# RS485.net
KiCad netlist of a schematic drawn in Altium Designer
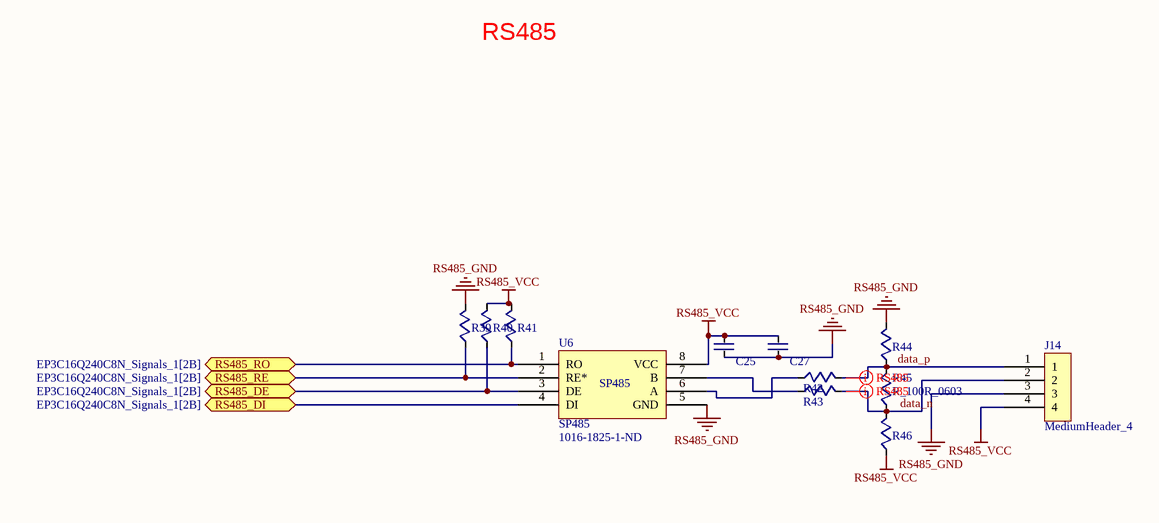
[diagram p0: RS485.SchDoc]

(export (version "E")
  (design (tool "Eeschema 10.0.6"))
  (components
    (comp (ref "C25")
      (value "100n Cer")
      (footprint "CN-SMD-0805")
      (description "CAP CER 0.1UF 25V 10% X7R 0805")
      (libsource (lib "EngineersLife") (part "CAPC0805_104"))
    )
    (comp (ref "C27")
      (value "10n Cer")
      (footprint "CN-SMD-0805")
      (description "CAP CER 10000PF 100V X7R 0805")
      (libsource (lib "EngineersLife") (part "CAPC0805_103"))
    )
    (comp (ref "J14")
      (value "MediumHeader_4")
      (footprint "Medium - Header 4")
      (libsource (lib "IO_Lib") (part "MediumHeader_4"))
    )
    (comp (ref "R39")
      (value "R_10K_0603")
      (footprint "RESC_0603")
      (description "RES 10.0K OHM 1/10W 1% 0603 SMD")
      (libsource (lib "IO_Lib") (part "RES0603_10K"))
    )
    (comp (ref "R40")
      (value "R_10K_0603")
      (footprint "RESC_0603")
      (description "RES 10.0K OHM 1/10W 1% 0603 SMD")
      (libsource (lib "IO_Lib") (part "RES0603_10K"))
    )
    (comp (ref "R41")
      (value "R_4K99_0603")
      (footprint "RESC_0603")
      (description "RES 4.99K OHM 1/10W 1% 0603 SMD")
      (libsource (lib "IO_Lib") (part "RES0603_4K99"))
    )
    (comp (ref "R42")
      (value "R_10K_0603")
      (footprint "RESC_0603")
      (description "RES 10.0K OHM 1/10W 1% 0603 SMD")
      (libsource (lib "IO_Lib") (part "RES0603_10K"))
    )
    (comp (ref "R43")
      (value "R_10R_0603")
      (footprint "RESC_0603")
      (description "RES 10.0 OHM 1/10W 0603 SMD")
      (libsource (lib "IO_Lib") (part "RES0603_10R"))
    )
    (comp (ref "R44")
      (value "R_2K_0603")
      (footprint "RESC_0603")
      (description "RES 2K OHM 1/10W 0603 SMD")
      (libsource (lib "IO_Lib") (part "RES0603_2K"))
    )
    (comp (ref "R45")
      (value "R_100R_0603")
      (footprint "RESC_0603")
      (description "RES 100 OHM 1/10W 5% 0603 SMD")
      (libsource (lib "IO_Lib") (part "RES0603_100R"))
    )
    (comp (ref "R46")
      (value "R_2K_0603")
      (footprint "RESC_0603")
      (description "RES 2K OHM 1/10W 0603 SMD")
      (libsource (lib "IO_Lib") (part "RES0603_2K"))
    )
    (comp (ref "U6")
      (value "SP485")
      (footprint "SOP8")
      (description "IC TXRX RS485 HALF DUPLEX 8SOIC")
      (fields (field (name "SUPPLIER PART NUMBER 1") "1016-1825-1-ND"))
      (libsource (lib "EngineersLife") (part "SP485"))
    )
  )
  (nets
    (net (code "1") (name "/RS485_DE") (class "Default")
      (node (ref "R40") (pin "1") (pinfunction "1_1") (pintype "passive"))
      (node (ref "U6") (pin "3") (pinfunction "DE_3") (pintype "passive"))
    )
    (net (code "2") (name "/RS485_DI") (class "Default")
      (node (ref "U6") (pin "4") (pinfunction "DI_4") (pintype "passive"))
    )
    (net (code "3") (name "/RS485_RE") (class "Default")
      (node (ref "R39") (pin "1") (pinfunction "1_1") (pintype "passive"))
      (node (ref "U6") (pin "2") (pinfunction "RE*_2") (pintype "passive"))
    )
    (net (code "4") (name "/RS485_RO") (class "Default")
      (node (ref "R41") (pin "1") (pinfunction "1_1") (pintype "passive"))
      (node (ref "U6") (pin "1") (pinfunction "RO_1") (pintype "passive"))
    )
    (net (code "5") (name "/data_n") (class "Default")
      (node (ref "J14") (pin "2") (pinfunction "2_2") (pintype "passive"))
      (node (ref "R43") (pin "2") (pinfunction "2_2") (pintype "passive"))
      (node (ref "R45") (pin "1") (pinfunction "1_1") (pintype "passive"))
      (node (ref "R46") (pin "2") (pinfunction "2_2") (pintype "passive"))
    )
    (net (code "6") (name "/data_p") (class "Default")
      (node (ref "J14") (pin "1") (pinfunction "1_1") (pintype "passive"))
      (node (ref "R42") (pin "2") (pinfunction "2_2") (pintype "passive"))
      (node (ref "R44") (pin "1") (pinfunction "1_1") (pintype "passive"))
      (node (ref "R45") (pin "2") (pinfunction "2_2") (pintype "passive"))
    )
    (net (code "7") (name "Net-(U6-A)") (class "Default")
      (node (ref "R42") (pin "1") (pinfunction "1_1") (pintype "passive"))
      (node (ref "U6") (pin "6") (pinfunction "A_6") (pintype "passive"))
    )
    (net (code "8") (name "Net-(U6-B)") (class "Default")
      (node (ref "R43") (pin "1") (pinfunction "1_1") (pintype "passive"))
      (node (ref "U6") (pin "7") (pinfunction "B_7") (pintype "passive"))
    )
    (net (code "9") (name "RS485_GND") (class "Default")
      (node (ref "C25") (pin "1") (pinfunction "1_1") (pintype "passive"))
      (node (ref "C27") (pin "1") (pinfunction "1_1") (pintype "passive"))
      (node (ref "J14") (pin "3") (pinfunction "3_3") (pintype "passive"))
      (node (ref "R39") (pin "2") (pinfunction "2_2") (pintype "passive"))
      (node (ref "R44") (pin "2") (pinfunction "2_2") (pintype "passive"))
      (node (ref "U6") (pin "5") (pinfunction "GND_5") (pintype "passive"))
    )
    (net (code "10") (name "RS485_VCC") (class "Default")
      (node (ref "C25") (pin "2") (pinfunction "2_2") (pintype "passive"))
      (node (ref "C27") (pin "2") (pinfunction "2_2") (pintype "passive"))
      (node (ref "J14") (pin "4") (pinfunction "4_4") (pintype "passive"))
      (node (ref "R40") (pin "2") (pinfunction "2_2") (pintype "passive"))
      (node (ref "R41") (pin "2") (pinfunction "2_2") (pintype "passive"))
      (node (ref "R46") (pin "1") (pinfunction "1_1") (pintype "passive"))
      (node (ref "U6") (pin "8") (pinfunction "VCC_8") (pintype "passive"))
    )
  )
)
